# Lightweight_2022_04.net
KiCad netlist of a schematic drawn in EAGLE
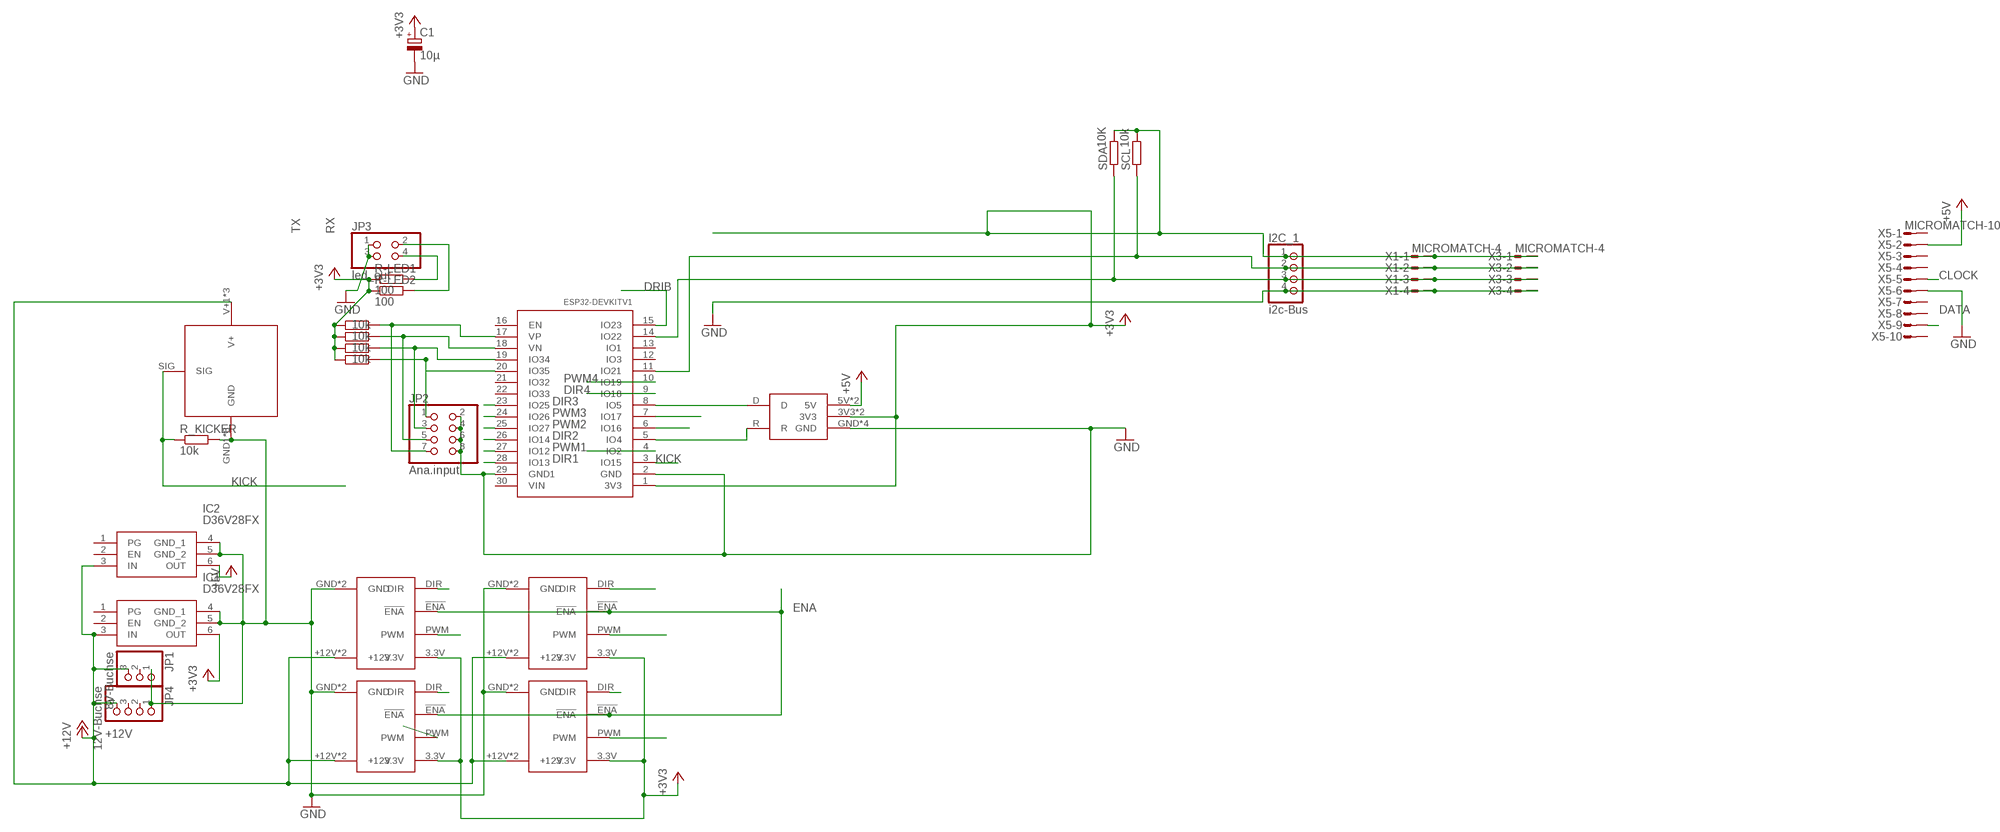
[diagram p0: schematic, sheet 1]

(export (version "E")
  (design (tool "Eeschema 10.0.6"))
  (components
    (comp (ref "C1")
      (value "10µ")
      (footprint "eagle-import:E2,5-6E")
      (libsource (lib "eagle-import") (part "CPOL-EUE2,5-6E"))
    )
    (comp (ref "I2C_1")
      (value "i2c-Bus")
      (footprint "eagle-import:1X04")
      (libsource (lib "eagle-import") (part "PINHD-1X4"))
    )
    (comp (ref "IC1")
      (value "D36V28FX")
      (footprint "eagle-import:D36V28FX")
      (libsource (lib "eagle-import") (part "D36V28FX"))
    )
    (comp (ref "IC2")
      (value "D36V28FX")
      (footprint "eagle-import:D36V28FX")
      (libsource (lib "eagle-import") (part "D36V28FX"))
    )
    (comp (ref "JP1")
      (value "8V-Buchse")
      (footprint "eagle-import:1X03")
      (libsource (lib "eagle-import") (part "PINHD-1X3"))
    )
    (comp (ref "JP2")
      (value "Ana.input")
      (footprint "eagle-import:2X04")
      (libsource (lib "eagle-import") (part "PINHD-2X4"))
    )
    (comp (ref "JP3")
      (value "led_out")
      (footprint "eagle-import:2X02")
      (libsource (lib "eagle-import") (part "PINHD-2X2"))
    )
    (comp (ref "JP4")
      (value "12V-Buchse")
      (footprint "eagle-import:1X04")
      (libsource (lib "eagle-import") (part "PINHD-1X4"))
    )
    (comp (ref "R-LED1")
      (value "100")
      (footprint "eagle-import:0207_10")
      (libsource (lib "eagle-import") (part "R-EU_0207/10"))
    )
    (comp (ref "R-LED2")
      (value "100")
      (footprint "eagle-import:0207_10")
      (libsource (lib "eagle-import") (part "R-EU_0207/10"))
    )
    (comp (ref "R_AD14")
      (value "10k")
      (footprint "eagle-import:0207_10")
      (libsource (lib "eagle-import") (part "R-EU_0207/10"))
    )
    (comp (ref "R_AD25")
      (value "10k")
      (footprint "eagle-import:0207_10")
      (libsource (lib "eagle-import") (part "R-EU_0207/10"))
    )
    (comp (ref "R_AD26")
      (value "10k")
      (footprint "eagle-import:0207_10")
      (libsource (lib "eagle-import") (part "R-EU_0207/10"))
    )
    (comp (ref "R_AD27")
      (value "10k")
      (footprint "eagle-import:0207_10")
      (libsource (lib "eagle-import") (part "R-EU_0207/10"))
    )
    (comp (ref "R_KICKER")
      (value "10k")
      (footprint "eagle-import:0207_10")
      (libsource (lib "eagle-import") (part "R-EU_0207/10"))
    )
    (comp (ref "SCL")
      (value "10k")
      (footprint "eagle-import:0207_10")
      (libsource (lib "eagle-import") (part "R-EU_0207/10"))
    )
    (comp (ref "SDA")
      (value "10K")
      (footprint "eagle-import:0207_10")
      (libsource (lib "eagle-import") (part "R-EU_0207/10"))
    )
    (comp (ref "U$5")
      (value "CANBUS")
      (footprint "eagle-import:CANBUS")
      (libsource (lib "eagle-import") (part "CANBUS"))
    )
    (comp (ref "U$11")
      (value "IFX9201BREAKOUT")
      (footprint "eagle-import:IFX9201BREAKOUT")
      (libsource (lib "eagle-import") (part "IFX9201BREAKOUT"))
    )
    (comp (ref "U$13")
      (value "ESP32DEVKITV1")
      (footprint "eagle-import:ESP32-DEVKITV1")
      (libsource (lib "eagle-import") (part "ESP32DEVKITV1"))
    )
    (comp (ref "U$14")
      (value "IFX9201BREAKOUT")
      (footprint "eagle-import:IFX9201BREAKOUT")
      (libsource (lib "eagle-import") (part "IFX9201BREAKOUT"))
    )
    (comp (ref "U$15")
      (value "IFX9201BREAKOUT")
      (footprint "eagle-import:IFX9201BREAKOUT")
      (libsource (lib "eagle-import") (part "IFX9201BREAKOUT"))
    )
    (comp (ref "U$16")
      (value "IFX9201BREAKOUT")
      (footprint "eagle-import:IFX9201BREAKOUT")
      (libsource (lib "eagle-import") (part "IFX9201BREAKOUT"))
    )
    (comp (ref "U$17")
      (value "KICKER")
      (footprint "eagle-import:KICKER")
      (libsource (lib "eagle-import") (part "KICKER"))
    )
    (comp (ref "X1")
      (value "MICROMATCH-4")
      (footprint "eagle-import:MICROMATCH-4")
      (fields (field (name "MPN") "7-215464-4"))
      (libsource (lib "eagle-import") (part "MICROMATCH-4"))
    )
    (comp (ref "X3")
      (value "MICROMATCH-4")
      (footprint "eagle-import:MICROMATCH-4")
      (fields (field (name "MPN") "7-215464-4"))
      (libsource (lib "eagle-import") (part "MICROMATCH-4"))
    )
    (comp (ref "X5")
      (value "MICROMATCH-10")
      (footprint "eagle-import:MICROMATCH-10")
      (fields (field (name "MF") "FARNELL") (field (name "MPN") "8-215464-0"))
      (libsource (lib "eagle-import") (part "MICROMATCH-10"))
    )
  )
  (nets
    (net (code "1") (name "+3V3") (class "Default")
      (node (ref "C1") (pin "+") (pinfunction "+_+") (pintype "passive"))
      (node (ref "I2C_1") (pin "1") (pinfunction "1_1") (pintype "passive"))
      (node (ref "IC1") (pin "6") (pinfunction "OUT_6") (pintype "bidirectional"))
      (node (ref "R-LED1") (pin "1") (pinfunction "1_1") (pintype "passive"))
      (node (ref "R-LED2") (pin "1") (pinfunction "1_1") (pintype "passive"))
      (node (ref "R_AD14") (pin "1") (pinfunction "1_1") (pintype "passive"))
      (node (ref "R_AD25") (pin "1") (pinfunction "1_1") (pintype "passive"))
      (node (ref "R_AD26") (pin "1") (pinfunction "1_1") (pintype "passive"))
      (node (ref "R_AD27") (pin "1") (pinfunction "1_1") (pintype "passive"))
      (node (ref "SCL") (pin "2") (pinfunction "2_2") (pintype "passive"))
      (node (ref "SDA") (pin "2") (pinfunction "2_2") (pintype "passive"))
      (node (ref "U$11") (pin "3.3V") (pinfunction "3.3V_3.3V") (pintype "bidirectional"))
      (node (ref "U$13") (pin "1") (pinfunction "3V3_1") (pintype "bidirectional"))
      (node (ref "U$14") (pin "3.3V") (pinfunction "3.3V_3.3V") (pintype "bidirectional"))
      (node (ref "U$15") (pin "3.3V") (pinfunction "3.3V_3.3V") (pintype "bidirectional"))
      (node (ref "U$16") (pin "3.3V") (pinfunction "3.3V_3.3V") (pintype "bidirectional"))
      (node (ref "U$5") (pin "3V3") (pinfunction "3V3_3V3") (pintype "bidirectional"))
      (node (ref "U$5") (pin "3V3_1") (pinfunction "3V3_3V3_1") (pintype "bidirectional"))
      (node (ref "X1") (pin "1") (pinfunction "S_1") (pintype "passive"))
      (node (ref "X3") (pin "1") (pinfunction "S_1") (pintype "passive"))
    )
    (net (code "2") (name "+5V") (class "Default")
      (node (ref "IC2") (pin "6") (pinfunction "OUT_6") (pintype "bidirectional"))
      (node (ref "U$5") (pin "5V") (pinfunction "5V_5V") (pintype "bidirectional"))
      (node (ref "U$5") (pin "5V_1") (pinfunction "5V_5V_1") (pintype "bidirectional"))
      (node (ref "X5") (pin "2") (pinfunction "S_2") (pintype "passive"))
    )
    (net (code "3") (name "+12V") (class "Default")
      (node (ref "IC1") (pin "3") (pinfunction "IN_3") (pintype "bidirectional"))
      (node (ref "IC2") (pin "3") (pinfunction "IN_3") (pintype "bidirectional"))
      (node (ref "JP1") (pin "3") (pinfunction "3_3") (pintype "passive"))
      (node (ref "JP4") (pin "4") (pinfunction "4_4") (pintype "passive"))
      (node (ref "U$11") (pin "+12V") (pinfunction "+12V_+12V") (pintype "bidirectional"))
      (node (ref "U$11") (pin "+12V2") (pinfunction "+12V_+12V2") (pintype "bidirectional"))
      (node (ref "U$14") (pin "+12V") (pinfunction "+12V_+12V") (pintype "bidirectional"))
      (node (ref "U$14") (pin "+12V2") (pinfunction "+12V_+12V2") (pintype "bidirectional"))
      (node (ref "U$15") (pin "+12V") (pinfunction "+12V_+12V") (pintype "bidirectional"))
      (node (ref "U$15") (pin "+12V2") (pinfunction "+12V_+12V2") (pintype "bidirectional"))
      (node (ref "U$16") (pin "+12V") (pinfunction "+12V_+12V") (pintype "bidirectional"))
      (node (ref "U$16") (pin "+12V2") (pinfunction "+12V_+12V2") (pintype "bidirectional"))
      (node (ref "U$17") (pin "V+1") (pinfunction "V+_V+1") (pintype "bidirectional"))
      (node (ref "U$17") (pin "V+2") (pinfunction "V+_V+2") (pintype "bidirectional"))
      (node (ref "U$17") (pin "V+3") (pinfunction "V+_V+3") (pintype "bidirectional"))
    )
    (net (code "4") (name "/CLOCK") (class "Default")
      (node (ref "I2C_1") (pin "3") (pinfunction "3_3") (pintype "passive"))
      (node (ref "SDA") (pin "1") (pinfunction "1_1") (pintype "passive"))
      (node (ref "U$13") (pin "14") (pinfunction "IO22_14") (pintype "bidirectional"))
      (node (ref "X1") (pin "3") (pinfunction "S_3") (pintype "passive"))
      (node (ref "X3") (pin "3") (pinfunction "S_3") (pintype "passive"))
      (node (ref "X5") (pin "5") (pinfunction "S_5") (pintype "passive"))
    )
    (net (code "5") (name "/DATA") (class "Default")
      (node (ref "I2C_1") (pin "2") (pinfunction "2_2") (pintype "passive"))
      (node (ref "SCL") (pin "1") (pinfunction "1_1") (pintype "passive"))
      (node (ref "U$13") (pin "11") (pinfunction "IO21_11") (pintype "bidirectional"))
      (node (ref "X1") (pin "2") (pinfunction "S_2") (pintype "passive"))
      (node (ref "X3") (pin "2") (pinfunction "S_2") (pintype "passive"))
      (node (ref "X5") (pin "9") (pinfunction "S_9") (pintype "passive"))
    )
    (net (code "6") (name "/DIR1") (class "Default")
      (node (ref "U$13") (pin "28") (pinfunction "IO13_28") (pintype "bidirectional"))
      (node (ref "U$16") (pin "DIR") (pinfunction "DIR_DIR") (pintype "bidirectional"))
    )
    (net (code "7") (name "/DIR2") (class "Default")
      (node (ref "U$13") (pin "26") (pinfunction "IO14_26") (pintype "bidirectional"))
      (node (ref "U$15") (pin "DIR") (pinfunction "DIR_DIR") (pintype "bidirectional"))
    )
    (net (code "8") (name "/DIR3") (class "Default")
      (node (ref "U$11") (pin "DIR") (pinfunction "DIR_DIR") (pintype "bidirectional"))
      (node (ref "U$13") (pin "23") (pinfunction "IO25_23") (pintype "bidirectional"))
    )
    (net (code "9") (name "/DIR4") (class "Default")
      (node (ref "U$13") (pin "9") (pinfunction "IO18_9") (pintype "bidirectional"))
      (node (ref "U$14") (pin "DIR") (pinfunction "DIR_DIR") (pintype "bidirectional"))
    )
    (net (code "10") (name "/DRIB") (class "Default")
      (node (ref "U$13") (pin "15") (pinfunction "IO23_15") (pintype "bidirectional"))
    )
    (net (code "11") (name "/ENA") (class "Default")
      (node (ref "U$11") (pin "!ENA") (pinfunction "~{ENA}_!ENA") (pintype "bidirectional"))
      (node (ref "U$13") (pin "4") (pinfunction "IO2_4") (pintype "bidirectional"))
      (node (ref "U$14") (pin "!ENA") (pinfunction "~{ENA}_!ENA") (pintype "bidirectional"))
      (node (ref "U$15") (pin "!ENA") (pinfunction "~{ENA}_!ENA") (pintype "bidirectional"))
      (node (ref "U$16") (pin "!ENA") (pinfunction "~{ENA}_!ENA") (pintype "bidirectional"))
    )
    (net (code "12") (name "/KICK") (class "Default")
      (node (ref "R_KICKER") (pin "1") (pinfunction "1_1") (pintype "passive"))
      (node (ref "U$13") (pin "3") (pinfunction "IO15_3") (pintype "bidirectional"))
      (node (ref "U$17") (pin "SIG") (pinfunction "SIG_SIG") (pintype "bidirectional"))
    )
    (net (code "13") (name "/PWM1") (class "Default")
      (node (ref "U$13") (pin "27") (pinfunction "IO12_27") (pintype "bidirectional"))
      (node (ref "U$16") (pin "PWM") (pinfunction "PWM_PWM") (pintype "bidirectional"))
    )
    (net (code "14") (name "/PWM2") (class "Default")
      (node (ref "U$13") (pin "25") (pinfunction "IO27_25") (pintype "bidirectional"))
      (node (ref "U$15") (pin "PWM") (pinfunction "PWM_PWM") (pintype "bidirectional"))
    )
    (net (code "15") (name "/PWM3") (class "Default")
      (node (ref "U$11") (pin "PWM") (pinfunction "PWM_PWM") (pintype "bidirectional"))
      (node (ref "U$13") (pin "24") (pinfunction "IO26_24") (pintype "bidirectional"))
    )
    (net (code "16") (name "/PWM4") (class "Default")
      (node (ref "U$13") (pin "10") (pinfunction "IO19_10") (pintype "bidirectional"))
      (node (ref "U$14") (pin "PWM") (pinfunction "PWM_PWM") (pintype "bidirectional"))
    )
    (net (code "17") (name "/RX") (class "Default")
      (node (ref "U$13") (pin "6") (pinfunction "IO16_6") (pintype "bidirectional"))
    )
    (net (code "18") (name "/TX") (class "Default")
      (node (ref "U$13") (pin "7") (pinfunction "IO17_7") (pintype "bidirectional"))
    )
    (net (code "19") (name "GND") (class "Default")
      (node (ref "C1") (pin "-") (pinfunction "-_-") (pintype "passive"))
      (node (ref "I2C_1") (pin "4") (pinfunction "4_4") (pintype "passive"))
      (node (ref "IC1") (pin "4") (pinfunction "GND_1_4") (pintype "bidirectional"))
      (node (ref "IC1") (pin "5") (pinfunction "GND_2_5") (pintype "bidirectional"))
      (node (ref "IC2") (pin "4") (pinfunction "GND_1_4") (pintype "bidirectional"))
      (node (ref "IC2") (pin "5") (pinfunction "GND_2_5") (pintype "bidirectional"))
      (node (ref "JP1") (pin "1") (pinfunction "1_1") (pintype "passive"))
      (node (ref "JP2") (pin "2") (pinfunction "2_2") (pintype "passive"))
      (node (ref "JP2") (pin "4") (pinfunction "4_4") (pintype "passive"))
      (node (ref "JP2") (pin "6") (pinfunction "6_6") (pintype "passive"))
      (node (ref "JP2") (pin "8") (pinfunction "8_8") (pintype "passive"))
      (node (ref "JP3") (pin "1") (pinfunction "1_1") (pintype "passive"))
      (node (ref "JP3") (pin "3") (pinfunction "3_3") (pintype "passive"))
      (node (ref "JP4") (pin "1") (pinfunction "1_1") (pintype "passive"))
      (node (ref "R_KICKER") (pin "2") (pinfunction "2_2") (pintype "passive"))
      (node (ref "U$11") (pin "GND") (pinfunction "GND_GND") (pintype "bidirectional"))
      (node (ref "U$11") (pin "GND2") (pinfunction "GND_GND2") (pintype "bidirectional"))
      (node (ref "U$13") (pin "2") (pinfunction "GND_2") (pintype "bidirectional"))
      (node (ref "U$13") (pin "29") (pinfunction "GND1_29") (pintype "bidirectional"))
      (node (ref "U$14") (pin "GND") (pinfunction "GND_GND") (pintype "bidirectional"))
      (node (ref "U$14") (pin "GND2") (pinfunction "GND_GND2") (pintype "bidirectional"))
      (node (ref "U$15") (pin "GND") (pinfunction "GND_GND") (pintype "bidirectional"))
      (node (ref "U$15") (pin "GND2") (pinfunction "GND_GND2") (pintype "bidirectional"))
      (node (ref "U$16") (pin "GND") (pinfunction "GND_GND") (pintype "bidirectional"))
      (node (ref "U$16") (pin "GND2") (pinfunction "GND_GND2") (pintype "bidirectional"))
      (node (ref "U$17") (pin "GND1") (pinfunction "GND_GND1") (pintype "bidirectional"))
      (node (ref "U$17") (pin "GND2") (pinfunction "GND_GND2") (pintype "bidirectional"))
      (node (ref "U$17") (pin "GND3") (pinfunction "GND_GND3") (pintype "bidirectional"))
      (node (ref "U$17") (pin "GND4") (pinfunction "GND_GND4") (pintype "bidirectional"))
      (node (ref "U$17") (pin "GND5") (pinfunction "GND_GND5") (pintype "bidirectional"))
      (node (ref "U$17") (pin "GND6") (pinfunction "GND_GND6") (pintype "bidirectional"))
      (node (ref "U$17") (pin "GND7") (pinfunction "GND_GND7") (pintype "bidirectional"))
      (node (ref "U$17") (pin "GND8") (pinfunction "GND_GND8") (pintype "bidirectional"))
      (node (ref "U$5") (pin "GND") (pinfunction "GND_GND") (pintype "bidirectional"))
      (node (ref "U$5") (pin "GND_1") (pinfunction "GND_GND_1") (pintype "bidirectional"))
      (node (ref "U$5") (pin "GND_2") (pinfunction "GND_GND_2") (pintype "bidirectional"))
      (node (ref "U$5") (pin "GND_3") (pinfunction "GND_GND_3") (pintype "bidirectional"))
      (node (ref "X1") (pin "4") (pinfunction "S_4") (pintype "passive"))
      (node (ref "X3") (pin "4") (pinfunction "S_4") (pintype "passive"))
      (node (ref "X5") (pin "6") (pinfunction "S_6") (pintype "passive"))
    )
    (net (code "20") (name "Net-(JP3-Pad2)") (class "Default")
      (node (ref "JP3") (pin "2") (pinfunction "2_2") (pintype "passive"))
      (node (ref "R-LED2") (pin "2") (pinfunction "2_2") (pintype "passive"))
    )
    (net (code "21") (name "Net-(JP3-Pad4)") (class "Default")
      (node (ref "JP3") (pin "4") (pinfunction "4_4") (pintype "passive"))
      (node (ref "R-LED1") (pin "2") (pinfunction "2_2") (pintype "passive"))
    )
    (net (code "22") (name "Net-(U$13-IO4)") (class "Default")
      (node (ref "U$13") (pin "5") (pinfunction "IO4_5") (pintype "bidirectional"))
      (node (ref "U$5") (pin "R") (pinfunction "R_R") (pintype "bidirectional"))
    )
    (net (code "23") (name "Net-(U$13-IO5)") (class "Default")
      (node (ref "U$13") (pin "8") (pinfunction "IO5_8") (pintype "bidirectional"))
      (node (ref "U$5") (pin "D") (pinfunction "D_D") (pintype "bidirectional"))
    )
    (net (code "24") (name "Net-(U$13-IO34)") (class "Default")
      (node (ref "JP2") (pin "3") (pinfunction "3_3") (pintype "passive"))
      (node (ref "R_AD27") (pin "2") (pinfunction "2_2") (pintype "passive"))
      (node (ref "U$13") (pin "19") (pinfunction "IO34_19") (pintype "bidirectional"))
    )
    (net (code "25") (name "Net-(U$13-IO35)") (class "Default")
      (node (ref "JP2") (pin "1") (pinfunction "1_1") (pintype "passive"))
      (node (ref "R_AD14") (pin "2") (pinfunction "2_2") (pintype "passive"))
      (node (ref "U$13") (pin "20") (pinfunction "IO35_20") (pintype "bidirectional"))
    )
    (net (code "26") (name "Net-(U$13-VN)") (class "Default")
      (node (ref "JP2") (pin "5") (pinfunction "5_5") (pintype "passive"))
      (node (ref "R_AD26") (pin "2") (pinfunction "2_2") (pintype "passive"))
      (node (ref "U$13") (pin "18") (pinfunction "VN_18") (pintype "bidirectional"))
    )
    (net (code "27") (name "Net-(U$13-VP)") (class "Default")
      (node (ref "JP2") (pin "7") (pinfunction "7_7") (pintype "passive"))
      (node (ref "R_AD25") (pin "2") (pinfunction "2_2") (pintype "passive"))
      (node (ref "U$13") (pin "17") (pinfunction "VP_17") (pintype "bidirectional"))
    )
    (net (code "28") (name "unconnected-(IC1-EN-Pad2)") (class "Default")
      (node (ref "IC1") (pin "2") (pinfunction "EN_2") (pintype "bidirectional"))
    )
    (net (code "29") (name "unconnected-(IC1-PG-Pad1)") (class "Default")
      (node (ref "IC1") (pin "1") (pinfunction "PG_1") (pintype "bidirectional"))
    )
    (net (code "30") (name "unconnected-(IC2-EN-Pad2)") (class "Default")
      (node (ref "IC2") (pin "2") (pinfunction "EN_2") (pintype "bidirectional"))
    )
    (net (code "31") (name "unconnected-(IC2-PG-Pad1)") (class "Default")
      (node (ref "IC2") (pin "1") (pinfunction "PG_1") (pintype "bidirectional"))
    )
    (net (code "32") (name "unconnected-(JP1-Pad2)") (class "Default")
      (node (ref "JP1") (pin "2") (pinfunction "2_2") (pintype "passive"))
    )
    (net (code "33") (name "unconnected-(JP4-Pad2)") (class "Default")
      (node (ref "JP4") (pin "2") (pinfunction "2_2") (pintype "passive"))
    )
    (net (code "34") (name "unconnected-(JP4-Pad3)") (class "Default")
      (node (ref "JP4") (pin "3") (pinfunction "3_3") (pintype "passive"))
    )
    (net (code "35") (name "unconnected-(U$13-EN-Pad16)") (class "Default")
      (node (ref "U$13") (pin "16") (pinfunction "EN_16") (pintype "bidirectional"))
    )
    (net (code "36") (name "unconnected-(U$13-IO1-Pad13)") (class "Default")
      (node (ref "U$13") (pin "13") (pinfunction "IO1_13") (pintype "bidirectional"))
    )
    (net (code "37") (name "unconnected-(U$13-IO3-Pad12)") (class "Default")
      (node (ref "U$13") (pin "12") (pinfunction "IO3_12") (pintype "bidirectional"))
    )
    (net (code "38") (name "unconnected-(U$13-IO32-Pad21)") (class "Default")
      (node (ref "U$13") (pin "21") (pinfunction "IO32_21") (pintype "bidirectional"))
    )
    (net (code "39") (name "unconnected-(U$13-IO33-Pad22)") (class "Default")
      (node (ref "U$13") (pin "22") (pinfunction "IO33_22") (pintype "bidirectional"))
    )
    (net (code "40") (name "unconnected-(U$13-VIN-Pad30)") (class "Default")
      (node (ref "U$13") (pin "30") (pinfunction "VIN_30") (pintype "bidirectional"))
    )
    (net (code "41") (name "unconnected-(X5A-S-Pad1)") (class "Default")
      (node (ref "X5") (pin "1") (pinfunction "S_1") (pintype "passive"))
    )
    (net (code "42") (name "unconnected-(X5B-S-Pad10)") (class "Default")
      (node (ref "X5") (pin "10") (pinfunction "S_10") (pintype "passive"))
    )
    (net (code "43") (name "unconnected-(X5D-S-Pad3)") (class "Default")
      (node (ref "X5") (pin "3") (pinfunction "S_3") (pintype "passive"))
    )
    (net (code "44") (name "unconnected-(X5E-S-Pad4)") (class "Default")
      (node (ref "X5") (pin "4") (pinfunction "S_4") (pintype "passive"))
    )
    (net (code "45") (name "unconnected-(X5H-S-Pad7)") (class "Default")
      (node (ref "X5") (pin "7") (pinfunction "S_7") (pintype "passive"))
    )
    (net (code "46") (name "unconnected-(X5I-S-Pad8)") (class "Default")
      (node (ref "X5") (pin "8") (pinfunction "S_8") (pintype "passive"))
    )
  )
)
